# Breakout_UVA.net
KiCad netlist of a schematic drawn in EAGLE
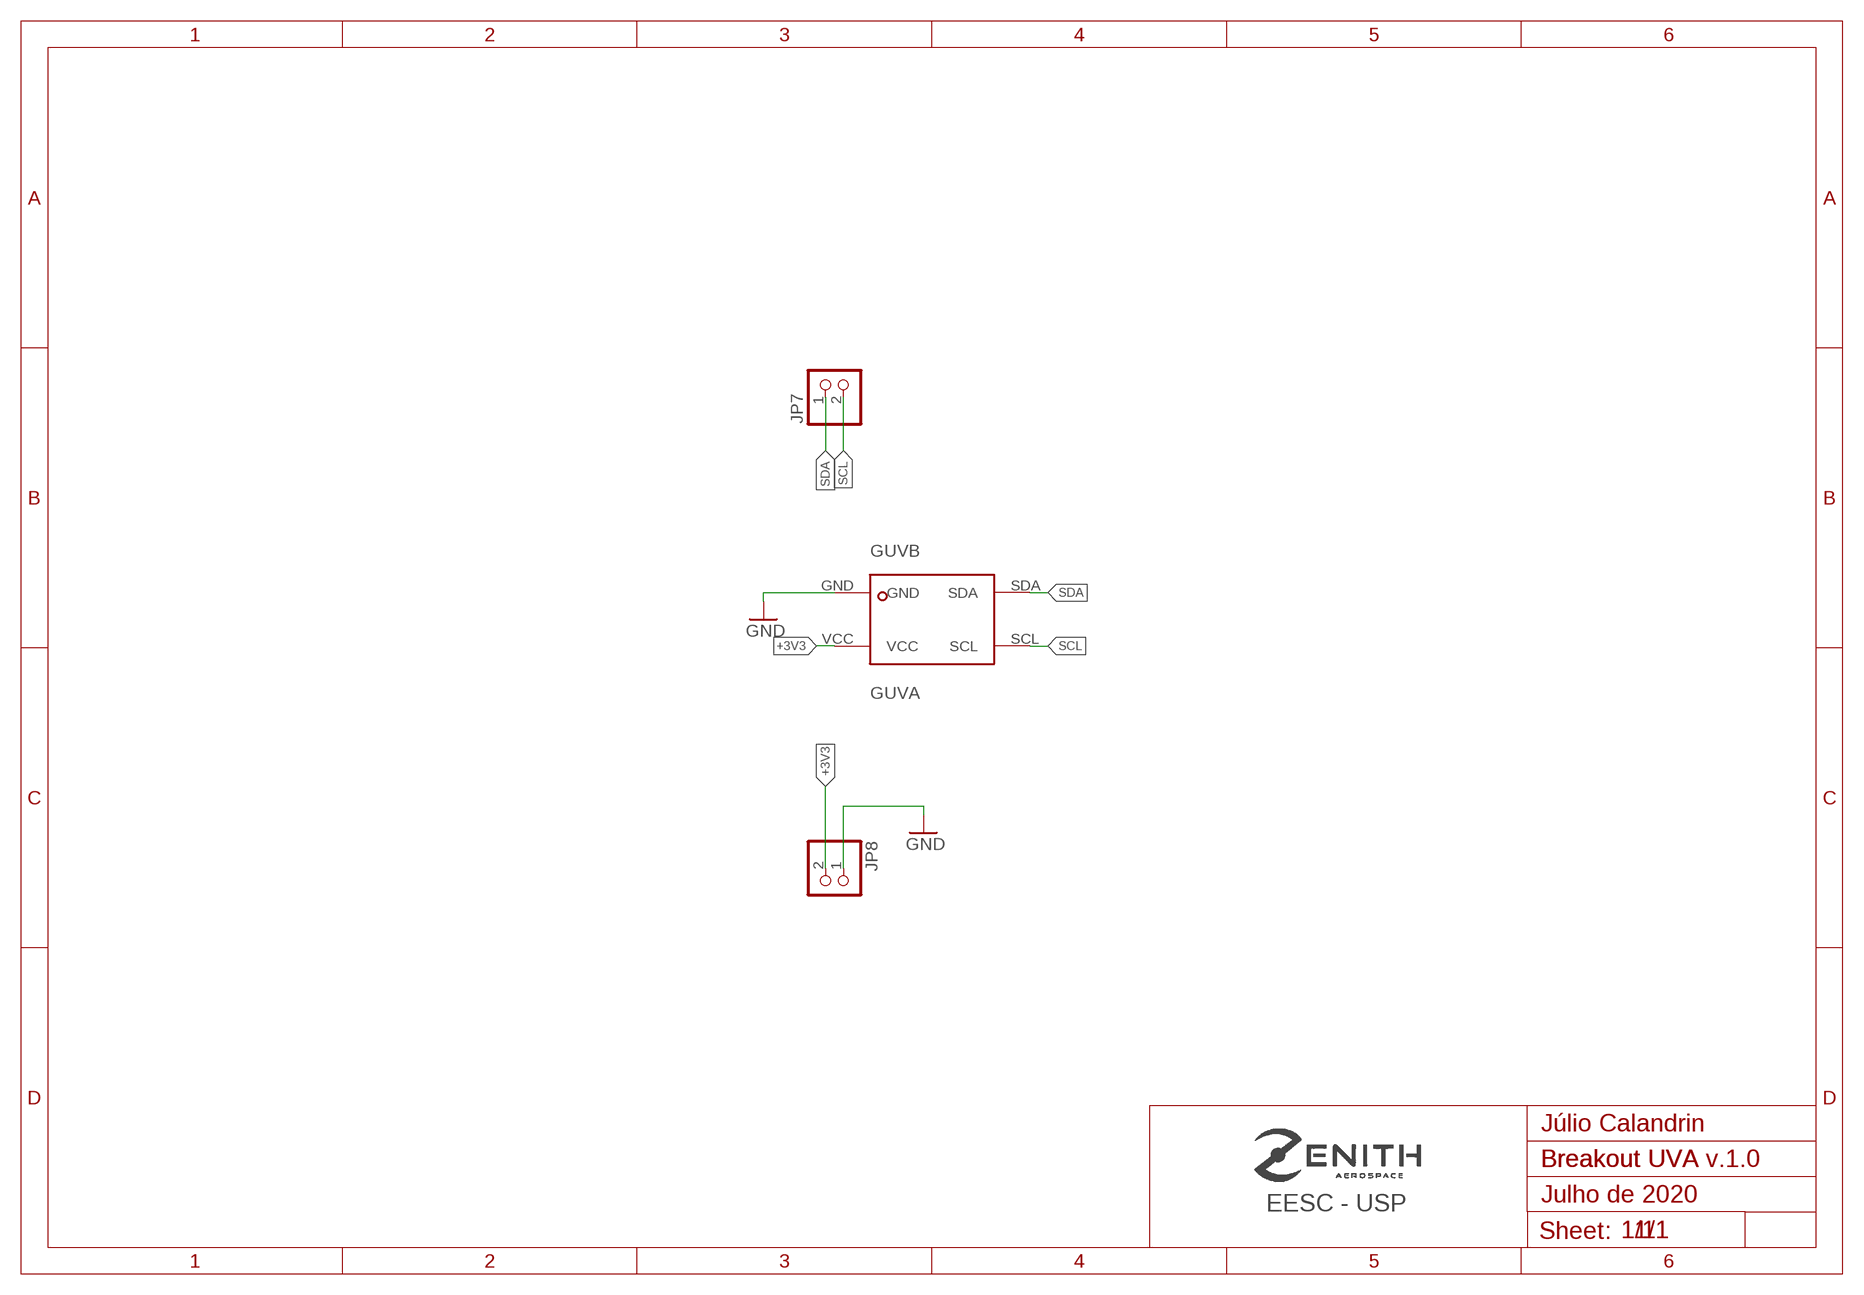
[diagram p0: schematic, sheet 1]

(export (version "E")
  (design (tool "Eeschema 10.0.6"))
  (components
    (comp (ref "GUVB")
      (value "GUVA")
      (footprint "eagle-import:GUV_A_B")
      (libsource (lib "eagle-import") (part "GUVA-C32SM"))
    )
    (comp (ref "JP7")
      (value "PINHD-1X2")
      (footprint "eagle-import:1X02(PAD_REDUZIDO)")
      (libsource (lib "eagle-import") (part "PINHD-1X2"))
    )
    (comp (ref "JP8")
      (value "PINHD-1X2")
      (footprint "eagle-import:1X02(PAD_REDUZIDO)")
      (libsource (lib "eagle-import") (part "PINHD-1X2"))
    )
  )
  (nets
    (net (code "1") (name "+3V3") (class "Default")
      (node (ref "GUVB") (pin "VCC") (pinfunction "VCC_VCC") (pintype "bidirectional"))
      (node (ref "JP8") (pin "2") (pinfunction "2_2") (pintype "passive"))
    )
    (net (code "2") (name "GND") (class "Default")
      (node (ref "GUVB") (pin "GND") (pinfunction "GND_GND") (pintype "bidirectional"))
      (node (ref "JP8") (pin "1") (pinfunction "1_1") (pintype "passive"))
    )
    (net (code "3") (name "SCL") (class "Default")
      (node (ref "GUVB") (pin "SCL") (pinfunction "SCL_SCL") (pintype "bidirectional"))
      (node (ref "JP7") (pin "2") (pinfunction "2_2") (pintype "passive"))
    )
    (net (code "4") (name "SDA") (class "Default")
      (node (ref "GUVB") (pin "SDA") (pinfunction "SDA_SDA") (pintype "bidirectional"))
      (node (ref "JP7") (pin "1") (pinfunction "1_1") (pintype "passive"))
    )
  )
)
